# OSC_RESET.net
KiCad netlist of a schematic drawn in Altium Designer
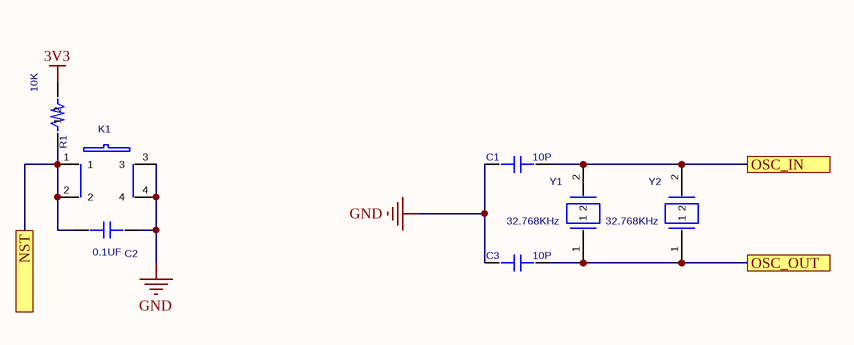
[diagram p0: OSC&RESET.SchDoc]

(export (version "E")
  (design (tool "Eeschema 10.0.6"))
  (components
    (comp (ref "C1")
      (value "10P")
      (footprint "RES_0603_FIRE")
      (description "0603")
      (fields (field (name "TOLERANCE") "+-5%") (field (name "Comment") "CAP_10P_0603_FIRE"))
      (libsource (lib "MINI-V3") (part "CAP_10P_0603_FIRE"))
    )
    (comp (ref "C2")
      (value "0.1UF")
      (footprint "CAP_0603_FIRE")
      (description "SURFACE MOUNT CAPACITOR 0.031 X 0.061 INCHES")
      (fields (field (name "Comment") "CAP_0.1UF_0603_FIRE"))
      (libsource (lib "MINI-V3") (part "CAP_0.1UF_0603_FIRE"))
    )
    (comp (ref "C3")
      (value "10P")
      (footprint "RES_0603_FIRE")
      (description "0603")
      (fields (field (name "TOLERANCE") "+-5%") (field (name "Comment") "CAP_10P_0603_FIRE"))
      (libsource (lib "MINI-V3") (part "CAP_10P_0603_FIRE"))
    )
    (comp (ref "K1") (value "KEY") (footprint "SW6.2/6.2-SMD") (libsource (lib "MINI-V3") (part "KEY")))
    (comp (ref "R1")
      (value "10K")
      (footprint "RES_0603_FIRE")
      (description "SURFACE MOUNT RESISTOR 0.031 X 0.061 INCHES, 1/10W")
      (fields (field (name "Comment") "RES_10K_0603_FIRE"))
      (libsource (lib "MINI-V3") (part "RES_10K_0603_FIRE"))
    )
    (comp (ref "Y1")
      (value "32.768KHz")
      (footprint "3215")
      (description "CRYSTAL")
      (fields (field (name "Comment") "XTAL_32.768KHZ_3215"))
      (libsource (lib "MINI-V3") (part "XTAL_32.768KHZ_3215"))
    )
    (comp (ref "Y2")
      (value "32.768KHz")
      (footprint "3215")
      (description "CRYSTAL")
      (fields (field (name "Comment") "XTAL_32.768KHZ_3215"))
      (libsource (lib "MINI-V3") (part "XTAL_32.768KHZ_3215"))
    )
  )
  (nets
    (net (code "1") (name "/NST") (class "Default")
      (node (ref "C2") (pin "2") (pinfunction "2_2") (pintype "passive"))
      (node (ref "K1") (pin "1") (pinfunction "1_1") (pintype "passive"))
      (node (ref "K1") (pin "2") (pinfunction "2_2") (pintype "passive"))
      (node (ref "R1") (pin "1") (pinfunction "1_1") (pintype "passive"))
    )
    (net (code "2") (name "/OSC_IN") (class "Default")
      (node (ref "C1") (pin "2") (pinfunction "2_2") (pintype "passive"))
      (node (ref "Y1") (pin "2") (pinfunction "2_2") (pintype "passive"))
      (node (ref "Y2") (pin "2") (pinfunction "2_2") (pintype "passive"))
    )
    (net (code "3") (name "/OSC_OUT") (class "Default")
      (node (ref "C3") (pin "2") (pinfunction "2_2") (pintype "passive"))
      (node (ref "Y1") (pin "1") (pinfunction "1_1") (pintype "passive"))
      (node (ref "Y2") (pin "1") (pinfunction "1_1") (pintype "passive"))
    )
    (net (code "4") (name "3V3") (class "Default")
      (node (ref "R1") (pin "2") (pinfunction "2_2") (pintype "passive"))
    )
    (net (code "5") (name "GND") (class "Default")
      (node (ref "C1") (pin "1") (pinfunction "1_1") (pintype "passive"))
      (node (ref "C2") (pin "1") (pinfunction "1_1") (pintype "passive"))
      (node (ref "C3") (pin "1") (pinfunction "1_1") (pintype "passive"))
      (node (ref "K1") (pin "3") (pinfunction "3_3") (pintype "passive"))
      (node (ref "K1") (pin "4") (pinfunction "4_4") (pintype "passive"))
    )
  )
)
